# Mobile_device_sheet4_sensor.net
KiCad netlist of a schematic drawn in Altium Designer
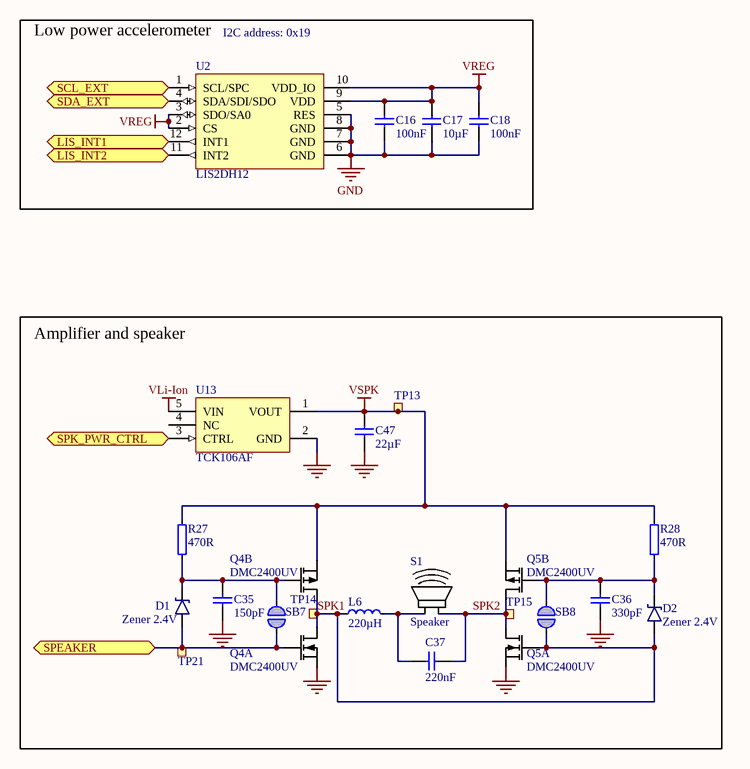
[diagram p0: Mobile_device_sheet4_sensor.SchDoc]

(export (version "E")
  (design (tool "Eeschema 10.0.6"))
  (components
    (comp (ref "C16")
      (value "100nF")
      (footprint "CAPC1005X04L")
      (description "Capacitor, X7R, ±10%")
      (fields (field (name "PART NUMBER") "C0402-100n") (field (name "PUBLISHER") "Nordic Semiconductor"))
      (libsource (lib "Nordic Passive DB") (part "CAP"))
    )
    (comp (ref "C17")
      (value "10µF")
      (footprint "CAPC1608X06L")
      (description "Capacitor, X5R, ±20%")
      (fields (field (name "PART NUMBER") "C0603-10µ") (field (name "PUBLISHER") "Nordic Semiconductor"))
      (libsource (lib "Nordic Passive DB") (part "CAP"))
    )
    (comp (ref "C18")
      (value "100nF")
      (footprint "CAPC1005X04L")
      (description "Capacitor, X7R, ±10%")
      (fields (field (name "PART NUMBER") "C0402-100n") (field (name "PUBLISHER") "Nordic Semiconductor"))
      (libsource (lib "Nordic Passive DB") (part "CAP"))
    )
    (comp (ref "C35")
      (value "150pF")
      (footprint "CAPC1005X04L")
      (description "Capacitor, NP0, ±5%")
      (fields (field (name "PART NUMBER") "C0402-150p") (field (name "PUBLISHER") "Nordic Semiconductor"))
      (libsource (lib "Nordic Passive DB") (part "CAP"))
    )
    (comp (ref "C36")
      (value "330pF")
      (footprint "CAPC1005X04L")
      (description "Capacitor, NP0, ±5%")
      (fields (field (name "PART NUMBER") "C0402-330p") (field (name "PUBLISHER") "Nordic Semiconductor"))
      (libsource (lib "Nordic Passive DB") (part "CAP"))
    )
    (comp (ref "C37")
      (value "220nF")
      (footprint "CAPC1005X04L")
      (description "Capacitor, X7R, ±10%")
      (fields (field (name "PART NUMBER") "C0402-220n") (field (name "PUBLISHER") "Nordic Semiconductor"))
      (libsource (lib "Nordic Passive DB") (part "CAP"))
    )
    (comp (ref "C47")
      (value "22µF")
      (footprint "CAPC1608X06L")
      (description "CAP CER 22UF 6.3V 20% X5R 0603")
      (fields
        (field (name "PART NUMBER") "C0603-22µ-6.3V")
        (field (name "MANUFACTURER") "Samsung")
        (field (name "PUBLISHER") "Nordic Semiconductor")
      )
      (libsource (lib "Nordic Passive DB") (part "CAP"))
    )
    (comp (ref "D1")
      (value "Zener 2.4V")
      (footprint "SOD-523")
      (description "Diode, Zener, 2.4V, 0.3W")
      (fields
        (field (name "PART NUMBER") "BZT52C2V4T")
        (field (name "MANUFACTURER") "Diodes Incorporated")
        (field (name "PUBLISHER") "Nordic Semiconductor")
      )
      (libsource (lib "Nordic Discrete DB") (part "D{colon}ZENER"))
    )
    (comp (ref "D2")
      (value "Zener 2.4V")
      (footprint "SOD-523")
      (description "Diode, Zener, 2.4V, 0.3W")
      (fields
        (field (name "PART NUMBER") "BZT52C2V4T")
        (field (name "MANUFACTURER") "Diodes Incorporated")
        (field (name "PUBLISHER") "Nordic Semiconductor")
      )
      (libsource (lib "Nordic Discrete DB") (part "D{colon}ZENER"))
    )
    (comp (ref "L6")
      (value "220µH")
      (footprint "INDP4040X25N")
      (description "Inductor, ±20%, 200mA, 2.76 Ohm")
      (fields
        (field (name "PART NUMBER") "L4040-220µ")
        (field (name "MANUFACTURER") "Bourns")
        (field (name "PUBLISHER") "Nordic Semiconductor")
      )
      (libsource (lib "Nordic Passive DB") (part "IND"))
    )
    (comp (ref "Q4")
      (value "DMC2400UV")
      (footprint "SOTFL50P162X60-6N")
      (description "Dual N & P Ch MOFET, 1.03A/0.7A, 480mOhm, 450mW")
      (fields
        (field (name "MANUFACTURER") "Diodes Incorporated")
        (field (name "PUBLISHER") "Nordic Semiconductor")
      )
      (libsource (lib "Nordic Discrete DB") (part "T{colon}FET-N/P-DUAL"))
    )
    (comp (ref "Q5")
      (value "DMC2400UV")
      (footprint "SOTFL50P162X60-6N")
      (description "Dual N & P Ch MOFET, 1.03A/0.7A, 480mOhm, 450mW")
      (fields
        (field (name "MANUFACTURER") "Diodes Incorporated")
        (field (name "PUBLISHER") "Nordic Semiconductor")
      )
      (libsource (lib "Nordic Discrete DB") (part "T{colon}FET-N/P-DUAL"))
    )
    (comp (ref "R27")
      (value "470R")
      (footprint "RESC1005X04L")
      (description "Resistor, ±1%, 0.063W")
      (fields (field (name "PART NUMBER") "R0402-470") (field (name "PUBLISHER") "Nordic Semiconductor"))
      (libsource (lib "Nordic Passive DB") (part "RES_1"))
    )
    (comp (ref "R28")
      (value "470R")
      (footprint "RESC1005X04L")
      (description "Resistor, ±1%, 0.063W")
      (fields (field (name "PART NUMBER") "R0402-470") (field (name "PUBLISHER") "Nordic Semiconductor"))
      (libsource (lib "Nordic Passive DB") (part "RES_1"))
    )
    (comp (ref "S1")
      (value "Speaker")
      (footprint "Speaker 15x11x3mm")
      (description "Speaker, SMD, 15.0mm x 11.0mm x 3.0mm, 0Hz-20kHz, 89dB, 8 ohm, 0.7W")
      (fields
        (field (name "PART NUMBER") "BMS1511F-11C-08H03P LF")
        (field (name "MANUFACTURER") "BeStar")
        (field (name "PUBLISHER") "Nordic Semiconductor")
      )
      (libsource (lib "Nordic Passive DB") (part "Speaker"))
    )
    (comp (ref "SB7")
      (value "Solderbridge")
      (footprint "Solderbridge")
      (fields (field (name "PUBLISHER") "Nordic Semiconductor"))
      (libsource (lib "Nordic Passive DB") (part "SOLDERBRIDGE"))
    )
    (comp (ref "SB8")
      (value "Solderbridge")
      (footprint "Solderbridge")
      (fields (field (name "PUBLISHER") "Nordic Semiconductor"))
      (libsource (lib "Nordic Passive DB") (part "SOLDERBRIDGE"))
    )
    (comp (ref "TP13")
      (value "Ø1.5mm,SMD")
      (footprint "TP_SMD_Ø1.5mm")
      (description "1.0mm circular SMD testpad")
      (fields
        (field (name "PART NUMBER") "TP_SMD_Ø1.5MM")
        (field (name "MANUFACTURER") "Nordic Semiconductor")
        (field (name "PUBLISHER") "Nordic Semiconductor")
      )
      (libsource (lib "Nordic Passive DB") (part "TESTPAD"))
    )
    (comp (ref "TP14")
      (value "Ø1.5mm,SMD")
      (footprint "TP_SMD_Ø1.5mm")
      (description "1.0mm circular SMD testpad")
      (fields
        (field (name "PART NUMBER") "TP_SMD_Ø1.5MM")
        (field (name "MANUFACTURER") "Nordic Semiconductor")
        (field (name "PUBLISHER") "Nordic Semiconductor")
      )
      (libsource (lib "") (part "TESTPAD_1"))
    )
    (comp (ref "TP15")
      (value "Ø1.5mm,SMD")
      (footprint "TP_SMD_Ø1.5mm")
      (description "1.0mm circular SMD testpad")
      (fields
        (field (name "PART NUMBER") "TP_SMD_Ø1.5MM")
        (field (name "MANUFACTURER") "Nordic Semiconductor")
        (field (name "PUBLISHER") "Nordic Semiconductor")
      )
      (libsource (lib "") (part "TESTPAD_3"))
    )
    (comp (ref "TP21")
      (value "Ø1.5mm,SMD")
      (footprint "TP_SMD_Ø1.5mm")
      (description "1.0mm circular SMD testpad")
      (fields
        (field (name "PART NUMBER") "TP_SMD_Ø1.5MM")
        (field (name "MANUFACTURER") "Nordic Semiconductor")
        (field (name "PUBLISHER") "Nordic Semiconductor")
      )
      (libsource (lib "") (part "TESTPAD_2"))
    )
    (comp (ref "U2")
      (value "LIS2DH12")
      (footprint "LGA50P200X200X100-12N")
      (description "3-axis - ±2g/±4g/±8g/±16g digital output femto accelerometer")
      (fields
        (field (name "MANUFACTURER") "STMicroelectronics")
        (field (name "PUBLISHER") "Nordic Semiconductor")
      )
      (libsource (lib "Nordic Active DB") (part "LIS2xx12"))
    )
    (comp (ref "U13")
      (value "TCK106AF")
      (footprint "SOT95P280X140-5N")
      (description "1.0 A Load Switch IC with Slew Rate Control Driver in Small Package")
      (fields
        (field (name "PART NUMBER") "TCK106AF,LF")
        (field (name "MANUFACTURER") "Toshiba")
        (field (name "PUBLISHER") "Nordic Semiconductor")
      )
      (libsource (lib "Nordic Active DB") (part "TCK10xAF"))
    )
  )
  (nets
    (net (code "1") (name "/LIS_INT1") (class "Default")
      (node (ref "U2") (pin "12") (pinfunction "INT1_12") (pintype "output"))
    )
    (net (code "2") (name "/LIS_INT2") (class "Default")
      (node (ref "U2") (pin "11") (pinfunction "INT2_11") (pintype "output"))
    )
    (net (code "3") (name "/SCL_EXT") (class "Default")
      (node (ref "U2") (pin "1") (pinfunction "SCL/SPC_1") (pintype "input"))
    )
    (net (code "4") (name "/SDA_EXT") (class "Default")
      (node (ref "U2") (pin "4") (pinfunction "SDA/SDI/SDO_4") (pintype "bidirectional"))
    )
    (net (code "5") (name "/SPEAKER") (class "Default")
      (node (ref "D1") (pin "1") (pinfunction "A_1") (pintype "passive"))
      (node (ref "Q4") (pin "2") (pinfunction "G1_2") (pintype "passive"))
      (node (ref "SB7") (pin "2") (pinfunction "1_2") (pintype "passive"))
      (node (ref "TP21") (pin "1") (pinfunction "1_1") (pintype "passive"))
    )
    (net (code "6") (name "/SPK1") (class "Default")
      (node (ref "D2") (pin "1") (pinfunction "A_1") (pintype "passive"))
      (node (ref "L6") (pin "1") (pinfunction "1_1") (pintype "passive"))
      (node (ref "Q4") (pin "3") (pinfunction "D2_3") (pintype "passive"))
      (node (ref "Q4") (pin "6") (pinfunction "D1_6") (pintype "passive"))
      (node (ref "Q5") (pin "2") (pinfunction "G1_2") (pintype "passive"))
      (node (ref "SB8") (pin "2") (pinfunction "1_2") (pintype "passive"))
      (node (ref "TP14") (pin "1") (pinfunction "1_1") (pintype "passive"))
    )
    (net (code "7") (name "/SPK2") (class "Default")
      (node (ref "C37") (pin "1") (pinfunction "1_1") (pintype "passive"))
      (node (ref "Q5") (pin "3") (pinfunction "D2_3") (pintype "passive"))
      (node (ref "Q5") (pin "6") (pinfunction "D1_6") (pintype "passive"))
      (node (ref "S1") (pin "2") (pinfunction "2_2") (pintype "passive"))
      (node (ref "TP15") (pin "1") (pinfunction "1_1") (pintype "passive"))
    )
    (net (code "8") (name "/SPK_PWR_CTRL") (class "Default")
      (node (ref "U13") (pin "3") (pinfunction "CTRL_3") (pintype "input"))
    )
    (net (code "9") (name "GND") (class "Default")
      (node (ref "C16") (pin "1") (pinfunction "1_1") (pintype "passive"))
      (node (ref "C17") (pin "1") (pinfunction "1_1") (pintype "passive"))
      (node (ref "C18") (pin "1") (pinfunction "1_1") (pintype "passive"))
      (node (ref "C35") (pin "1") (pinfunction "1_1") (pintype "passive"))
      (node (ref "C36") (pin "1") (pinfunction "1_1") (pintype "passive"))
      (node (ref "C47") (pin "1") (pinfunction "1_1") (pintype "passive"))
      (node (ref "Q4") (pin "1") (pinfunction "S1_1") (pintype "passive"))
      (node (ref "Q5") (pin "1") (pinfunction "S1_1") (pintype "passive"))
      (node (ref "U13") (pin "2") (pinfunction "GND_2") (pintype "power_in"))
      (node (ref "U2") (pin "5") (pinfunction "RES_5") (pintype "passive"))
      (node (ref "U2") (pin "6") (pinfunction "GND_6") (pintype "power_in"))
      (node (ref "U2") (pin "7") (pinfunction "GND_7") (pintype "power_in"))
      (node (ref "U2") (pin "8") (pinfunction "GND_8") (pintype "power_in"))
    )
    (net (code "10") (name "Net-(C37-Pad2)") (class "Default")
      (node (ref "C37") (pin "2") (pinfunction "2_2") (pintype "passive"))
      (node (ref "L6") (pin "2") (pinfunction "2_2") (pintype "passive"))
      (node (ref "S1") (pin "1") (pinfunction "1_1") (pintype "passive"))
    )
    (net (code "11") (name "Net-(D1-C)") (class "Default")
      (node (ref "C35") (pin "2") (pinfunction "2_2") (pintype "passive"))
      (node (ref "D1") (pin "3") (pinfunction "C_3") (pintype "passive"))
      (node (ref "Q4") (pin "5") (pinfunction "G2_5") (pintype "passive"))
      (node (ref "R27") (pin "2") (pinfunction "2_2") (pintype "passive"))
      (node (ref "SB7") (pin "1") (pinfunction "0_1") (pintype "passive"))
    )
    (net (code "12") (name "Net-(D2-C)") (class "Default")
      (node (ref "C36") (pin "2") (pinfunction "2_2") (pintype "passive"))
      (node (ref "D2") (pin "3") (pinfunction "C_3") (pintype "passive"))
      (node (ref "Q5") (pin "5") (pinfunction "G2_5") (pintype "passive"))
      (node (ref "R28") (pin "2") (pinfunction "2_2") (pintype "passive"))
      (node (ref "SB8") (pin "1") (pinfunction "0_1") (pintype "passive"))
    )
    (net (code "13") (name "VLi-Ion") (class "Default")
      (node (ref "U13") (pin "5") (pinfunction "VIN_5") (pintype "power_in"))
    )
    (net (code "14") (name "VREG") (class "Default")
      (node (ref "C16") (pin "2") (pinfunction "2_2") (pintype "passive"))
      (node (ref "C17") (pin "2") (pinfunction "2_2") (pintype "passive"))
      (node (ref "C18") (pin "2") (pinfunction "2_2") (pintype "passive"))
      (node (ref "U2") (pin "10") (pinfunction "VDD_IO_10") (pintype "power_in"))
      (node (ref "U2") (pin "2") (pinfunction "CS_2") (pintype "input"))
      (node (ref "U2") (pin "3") (pinfunction "SDO/SA0_3") (pintype "bidirectional"))
      (node (ref "U2") (pin "9") (pinfunction "VDD_9") (pintype "power_in"))
    )
    (net (code "15") (name "VSPK") (class "Default")
      (node (ref "C47") (pin "2") (pinfunction "2_2") (pintype "passive"))
      (node (ref "Q4") (pin "4") (pinfunction "S2_4") (pintype "passive"))
      (node (ref "Q5") (pin "4") (pinfunction "S2_4") (pintype "passive"))
      (node (ref "R27") (pin "1") (pinfunction "1_1") (pintype "passive"))
      (node (ref "R28") (pin "1") (pinfunction "1_1") (pintype "passive"))
      (node (ref "TP13") (pin "1") (pinfunction "1_1") (pintype "passive"))
      (node (ref "U13") (pin "1") (pinfunction "VOUT_1") (pintype "power_in"))
    )
    (net (code "16") (name "unconnected-(U13-NC-Pad4)") (class "Default")
      (node (ref "U13") (pin "4") (pinfunction "NC_4") (pintype "passive"))
    )
  )
)
